# mcp661.net
KiCad netlist of a schematic drawn in EAGLE
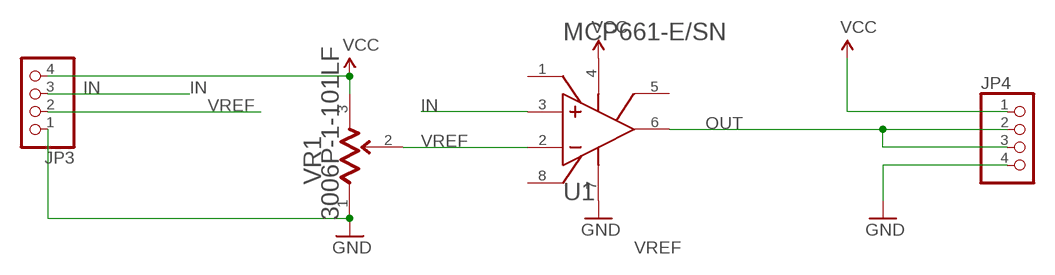
[diagram p0: schematic, sheet 1]

(export (version "E")
  (design (tool "Eeschema 10.0.6"))
  (components
    (comp (ref "JP3")
      (value "PINHD-1X4")
      (footprint "eagle-import:1X04")
      (libsource (lib "eagle-import") (part "PINHD-1X4"))
    )
    (comp (ref "JP4")
      (value "PINHD-1X4")
      (footprint "eagle-import:1X04")
      (libsource (lib "eagle-import") (part "PINHD-1X4"))
    )
    (comp (ref "U1")
      (value "MICROCHIP_MCP661-E-SNMICROCHIP_MCP661-E-SN_0_2")
      (footprint "eagle-import:MICROCHIP_MCP661-E-SN_2")
      (fields (field (name "MF") "Microchip") (field (name "MPN") "MCP661-E/SN"))
      (libsource (lib "eagle-import") (part "MICROCHIP_MCP661-E-SNMICROCHIP_MCP661-E-SN_0_2"))
    )
    (comp (ref "VR1")
      (value "BOURNS_3006P-1-101LFBOURNS_3006P-1-101LF_0_0")
      (footprint "eagle-import:BOURNS_3006P-1-101LF_0")
      (fields
        (field (name "DIGIKEY_PART_NUMBER") "3006P-101LF-ND")
        (field (name "MF") "Bourns")
        (field (name "MOUSER_PART_NUMBER") "652-3006P-1-101-LF")
      )
      (libsource (lib "eagle-import") (part "BOURNS_3006P-1-101LFBOURNS_3006P-1-101LF_0_0"))
    )
  )
  (nets
    (net (code "1") (name "/IN") (class "Default")
      (node (ref "JP3") (pin "3") (pinfunction "3_3") (pintype "passive"))
      (node (ref "U1") (pin "3") (pinfunction "VIN+_3") (pintype "input"))
    )
    (net (code "2") (name "/OUT") (class "Default")
      (node (ref "JP4") (pin "2") (pinfunction "2_2") (pintype "passive"))
      (node (ref "JP4") (pin "3") (pinfunction "3_3") (pintype "passive"))
      (node (ref "U1") (pin "6") (pinfunction "VOUT_6") (pintype "output"))
    )
    (net (code "3") (name "/VREF") (class "Default")
      (node (ref "JP3") (pin "2") (pinfunction "2_2") (pintype "passive"))
      (node (ref "U1") (pin "2") (pinfunction "VIN-_2") (pintype "input"))
      (node (ref "VR1") (pin "2") (pinfunction "WIPER_2") (pintype "bidirectional"))
    )
    (net (code "4") (name "GND") (class "Default")
      (node (ref "JP3") (pin "1") (pinfunction "1_1") (pintype "passive"))
      (node (ref "JP4") (pin "4") (pinfunction "4_4") (pintype "passive"))
      (node (ref "U1") (pin "7") (pinfunction "VDD_7") (pintype "power_in"))
      (node (ref "VR1") (pin "1") (pinfunction "CCW_1") (pintype "bidirectional"))
    )
    (net (code "5") (name "VCC") (class "Default")
      (node (ref "JP3") (pin "4") (pinfunction "4_4") (pintype "passive"))
      (node (ref "JP4") (pin "1") (pinfunction "1_1") (pintype "passive"))
      (node (ref "U1") (pin "4") (pinfunction "VSS_4") (pintype "power_in"))
      (node (ref "VR1") (pin "3") (pinfunction "CW_3") (pintype "bidirectional"))
    )
    (net (code "6") (name "unconnected-(U1-1_NC-Pad1)") (class "Default")
      (node (ref "U1") (pin "1") (pinfunction "1_NC_1") (pintype "passive"))
    )
    (net (code "7") (name "unconnected-(U1-2_NC-Pad5)") (class "Default")
      (node (ref "U1") (pin "5") (pinfunction "2_NC_5") (pintype "passive"))
    )
    (net (code "8") (name "unconnected-(U1-3_NC-Pad8)") (class "Default")
      (node (ref "U1") (pin "8") (pinfunction "3_NC_8") (pintype "passive"))
    )
  )
)
